# LSM6DSRXTR.net
KiCad netlist of a schematic drawn in Altium Designer
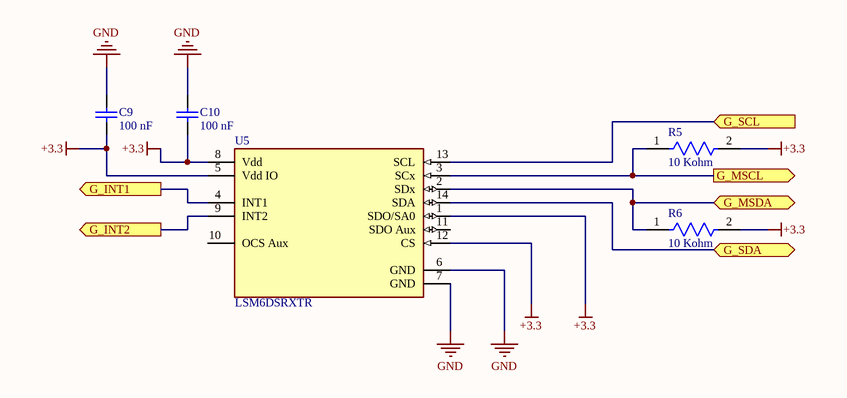
[diagram p0: LSM6DSRXTR.SchDoc]

(export (version "E")
  (design (tool "Eeschema 10.0.6"))
  (components
    (comp (ref "C9")
      (value "100 nF")
      (footprint "CAPC1005X55X25NL05T10")
      (fields (field (name "MANUFACTURER") "Murata") (field (name "PART NUMBER") "GRM155F50J684ZE01D"))
      (libsource (lib "Altium Content Vault") (part "CAP"))
    )
    (comp (ref "C10")
      (value "100 nF")
      (footprint "CAPC1005X55X25NL05T10")
      (fields (field (name "MANUFACTURER") "Murata") (field (name "PART NUMBER") "GRM155F50J684ZE01D"))
      (libsource (lib "Altium Content Vault") (part "CAP"))
    )
    (comp (ref "R5")
      (value "10 Kohm")
      (footprint "FP-RC1005-IPC_C")
      (description "Res Thick Film 0402 1.87kΩ 1% 0.063W ±100ppm/°C Molded SMD T/R")
      (fields (field (name "TOLERANCE") "1%"))
      (libsource (lib "Altium Content Vault") (part "1029c3af85768c4190bb7ad29bc67b5"))
    )
    (comp (ref "R6")
      (value "10 Kohm")
      (footprint "FP-RC1005-IPC_C")
      (description "Res Thick Film 0402 1.87kΩ 1% 0.063W ±100ppm/°C Molded SMD T/R")
      (fields (field (name "TOLERANCE") "1%"))
      (libsource (lib "Altium Content Vault") (part "1029c3af85768c4190bb7ad29bc67b5"))
    )
    (comp (ref "U5")
      (value "LSM6DSRXTR")
      (footprint "FP-LGA-14L-DM00249496-MFG")
      (description "CONSUMER MEMS")
      (libsource (lib "Altium Content Vault") (part "541766176f9193a0aeca2d3d8f6bee9"))
    )
  )
  (nets
    (net (code "1") (name "+3.3") (class "Default")
      (node (ref "C10") (pin "2") (pinfunction "2_2") (pintype "passive"))
      (node (ref "C9") (pin "2") (pinfunction "2_2") (pintype "passive"))
      (node (ref "R5") (pin "2") (pinfunction "2_2") (pintype "passive"))
      (node (ref "R6") (pin "2") (pinfunction "2_2") (pintype "passive"))
      (node (ref "U5") (pin "1") (pinfunction "SDO/SA0_1") (pintype "bidirectional"))
      (node (ref "U5") (pin "12") (pinfunction "CS_12") (pintype "input"))
      (node (ref "U5") (pin "5") (pinfunction "Vdd_IO_5") (pintype "power_in"))
      (node (ref "U5") (pin "8") (pinfunction "Vdd_8") (pintype "power_in"))
    )
    (net (code "2") (name "/G_INT1") (class "Default")
      (node (ref "U5") (pin "4") (pinfunction "INT1_4") (pintype "passive"))
    )
    (net (code "3") (name "/G_INT2") (class "Default")
      (node (ref "U5") (pin "9") (pinfunction "INT2_9") (pintype "passive"))
    )
    (net (code "4") (name "/G_MSCL") (class "Default")
      (node (ref "R5") (pin "1") (pinfunction "1_1") (pintype "passive"))
      (node (ref "U5") (pin "3") (pinfunction "SCx_3") (pintype "input"))
    )
    (net (code "5") (name "/G_MSDA") (class "Default")
      (node (ref "R6") (pin "1") (pinfunction "1_1") (pintype "passive"))
      (node (ref "U5") (pin "2") (pinfunction "SDx_2") (pintype "bidirectional"))
    )
    (net (code "6") (name "/G_SCL") (class "Default")
      (node (ref "U5") (pin "13") (pinfunction "SCL_13") (pintype "input"))
    )
    (net (code "7") (name "/G_SDA") (class "Default")
      (node (ref "U5") (pin "14") (pinfunction "SDA_14") (pintype "bidirectional"))
    )
    (net (code "8") (name "GND") (class "Default")
      (node (ref "C10") (pin "1") (pinfunction "1_1") (pintype "passive"))
      (node (ref "C9") (pin "1") (pinfunction "1_1") (pintype "passive"))
      (node (ref "U5") (pin "6") (pinfunction "GND_6") (pintype "power_in"))
      (node (ref "U5") (pin "7") (pinfunction "GND_7") (pintype "power_in"))
    )
    (net (code "9") (name "unconnected-(U5-OCS_Aux-Pad10)") (class "Default")
      (node (ref "U5") (pin "10") (pinfunction "OCS_Aux_10") (pintype "passive"))
    )
    (net (code "10") (name "unconnected-(U5-SDO_Aux-Pad11)") (class "Default")
      (node (ref "U5") (pin "11") (pinfunction "SDO_Aux_11") (pintype "bidirectional"))
    )
  )
)
